# PowerConnections.net
KiCad netlist of a schematic drawn in Altium Designer
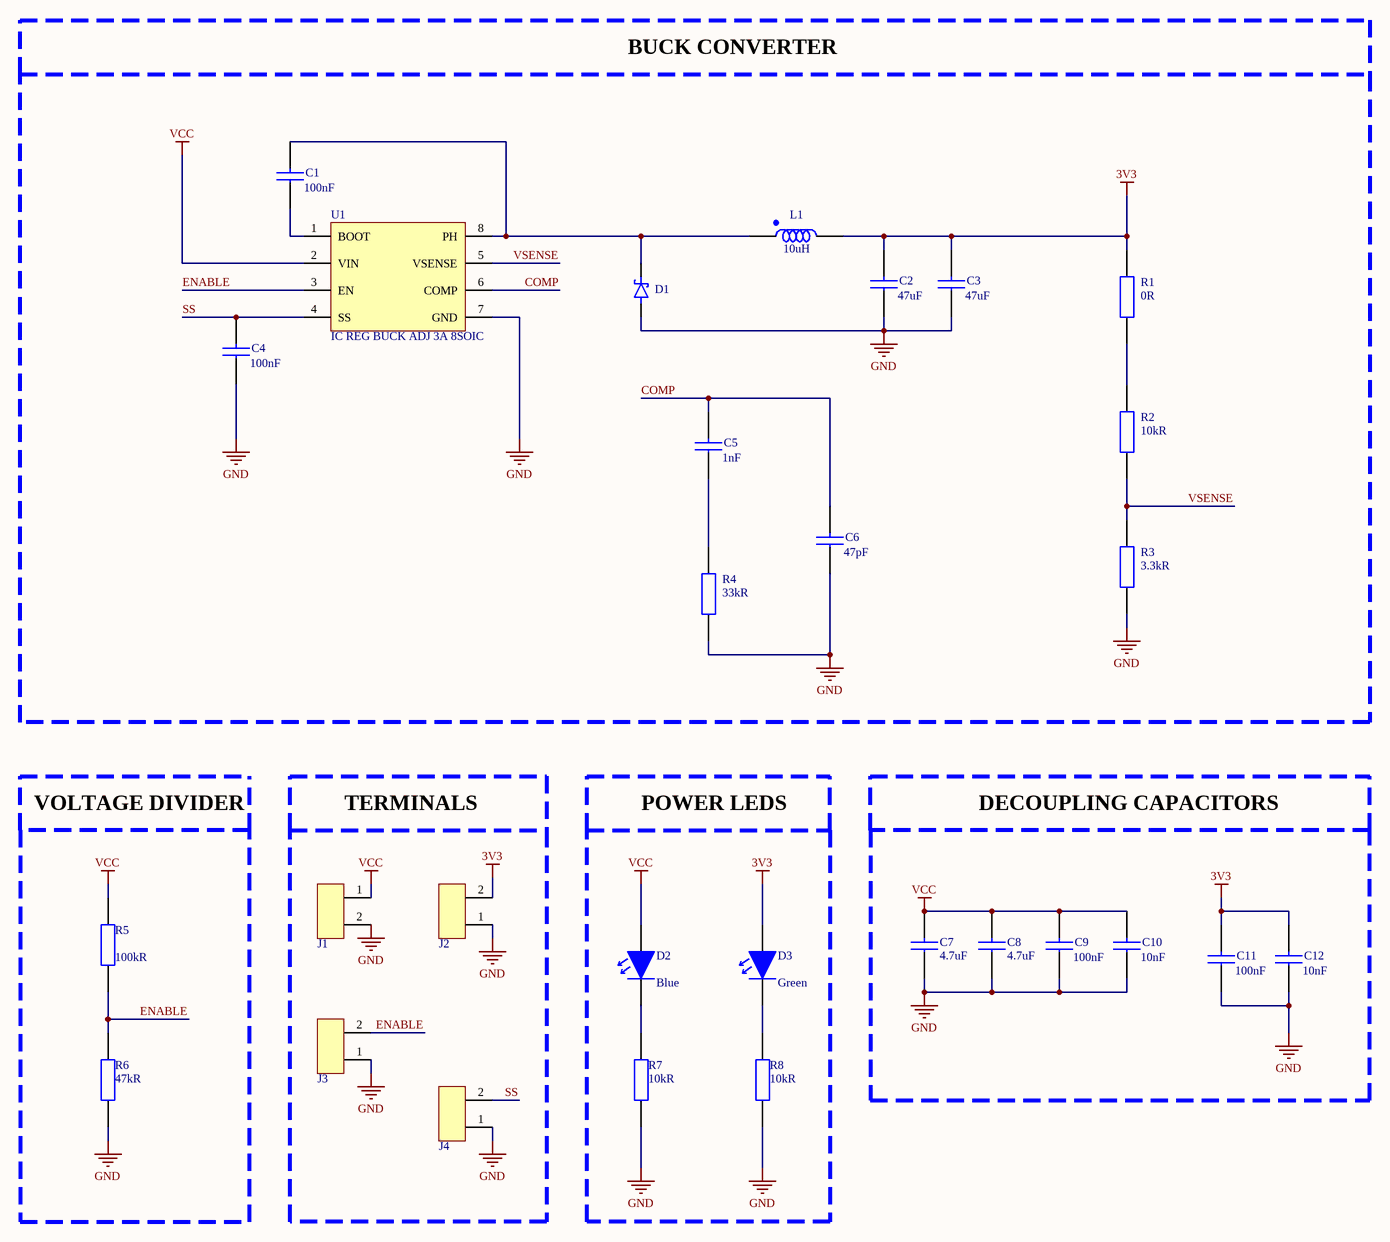
[diagram p0: PowerConnections.SchDoc]

(export (version "E")
  (design (tool "Eeschema 10.0.6"))
  (components
    (comp (ref "C1")
      (value "C1206C104J5RAC7800")
      (footprint "CAP_1206")
      (description "CAP CER 0.1UF 50V X7R 1206")
      (fields
        (field (name "MANUFACTURER") "Kyocera AVX")
        (field (name "MANUFACTURER PART NUMBER") "12065C104JAT2A")
        (field (name "CAPACITANCE") "100nF")
        (field (name "DESIGNEDBY") "Aslı Kurt")
      )
      (libsource (lib "Capacitors") (part "CAP CER 100nF 1206"))
    )
    (comp (ref "C2")
      (value "GMC31X5R476M25NT")
      (footprint "CAP_1206")
      (description "CAP CER 47UF 25V X5R 1206")
      (fields
        (field (name "MANUFACTURER") "Cal-Chip Electronics")
        (field (name "TOLERANCE") "20%")
        (field (name "CAPACITANCE") "47uF")
        (field (name "DESIGNEDBY") "Aslı Kurt")
      )
      (libsource (lib "Capacitors") (part "CAP CER 47uF 1206"))
    )
    (comp (ref "C3")
      (value "GMC31X5R476M25NT")
      (footprint "CAP_1206")
      (description "CAP CER 47UF 25V X5R 1206")
      (fields
        (field (name "MANUFACTURER") "Cal-Chip Electronics")
        (field (name "TOLERANCE") "20%")
        (field (name "CAPACITANCE") "47uF")
        (field (name "DESIGNEDBY") "Aslı Kurt")
      )
      (libsource (lib "Capacitors") (part "CAP CER 47uF 1206"))
    )
    (comp (ref "C4")
      (value "C1206C104J5RAC7800")
      (footprint "CAP_1206")
      (description "CAP CER 0.1UF 50V X7R 1206")
      (fields
        (field (name "MANUFACTURER") "Kyocera AVX")
        (field (name "MANUFACTURER PART NUMBER") "12065C104JAT2A")
        (field (name "CAPACITANCE") "100nF")
        (field (name "DESIGNEDBY") "Aslı Kurt")
      )
      (libsource (lib "Capacitors") (part "CAP CER 100nF 1206"))
    )
    (comp (ref "C5")
      (value "C3216C0G2J102J085AA")
      (footprint "CAP_1206")
      (description "CAP CER 1nF 1206")
      (fields
        (field (name "MANUFACTURER") "TDK")
        (field (name "CAPACITANCE") "1nF")
        (field (name "DESIGNEDBY") "Aslı Kurt")
      )
      (libsource (lib "Capacitors") (part "CAP CER 1nF 1206"))
    )
    (comp (ref "C6")
      (value "C1206C470J5GAC7800")
      (footprint "CAP_1206")
      (description "CAP CER 47PF 50V C0G/NP0 1206")
      (fields
        (field (name "MANUFACTURER") "KEMET")
        (field (name "MANUFACTURER PART NUMBER") "C1206C470J5GACTU")
        (field (name "CAPACITANCE") "47pF")
      )
      (libsource (lib "Capacitors") (part "CAP CER 47pF 1206"))
    )
    (comp (ref "C7")
      (value "CL21A475KAQNNNE")
      (footprint "CAP_0805")
      (description "CAP CER 4.7uF %10 0805")
      (fields
        (field (name "MANUFACTURER") "Samsung")
        (field (name "TOLERANCE") "10%")
        (field (name "CAPACITANCE") "4.7uF")
        (field (name "DESIGNED BY") "BERK")
      )
      (libsource (lib "Capacitors") (part "CAP CER 4.7uF 0805"))
    )
    (comp (ref "C8")
      (value "CL21A475KAQNNNE")
      (footprint "CAP_0805")
      (description "CAP CER 4.7uF %10 0805")
      (fields
        (field (name "MANUFACTURER") "Samsung")
        (field (name "TOLERANCE") "10%")
        (field (name "CAPACITANCE") "4.7uF")
        (field (name "DESIGNED BY") "BERK")
      )
      (libsource (lib "Capacitors") (part "CAP CER 4.7uF 0805"))
    )
    (comp (ref "C9")
      (value "C1206C104J5RAC7800")
      (footprint "CAP_1206")
      (description "CAP CER 0.1UF 50V X7R 1206")
      (fields
        (field (name "MANUFACTURER") "Kyocera AVX")
        (field (name "MANUFACTURER PART NUMBER") "12065C104JAT2A")
        (field (name "CAPACITANCE") "100nF")
        (field (name "DESIGNEDBY") "Aslı Kurt")
      )
      (libsource (lib "Capacitors") (part "CAP CER 100nF 1206"))
    )
    (comp (ref "C10")
      (value "C3216C0G2J103J160AA")
      (footprint "CAP_1206")
      (description "CAP CER 10nF 1206")
      (fields
        (field (name "MANUFACTURER") "TDK")
        (field (name "CAPACITANCE") "10nF")
        (field (name "DESIGNEDBY") "Aslı Kurt")
      )
      (libsource (lib "Capacitors") (part "CAP CER 10nF 1206"))
    )
    (comp (ref "C11")
      (value "C1206C104J5RAC7800")
      (footprint "CAP_1206")
      (description "CAP CER 0.1UF 50V X7R 1206")
      (fields
        (field (name "MANUFACTURER") "Kyocera AVX")
        (field (name "MANUFACTURER PART NUMBER") "12065C104JAT2A")
        (field (name "CAPACITANCE") "100nF")
        (field (name "DESIGNEDBY") "Aslı Kurt")
      )
      (libsource (lib "Capacitors") (part "CAP CER 100nF 1206"))
    )
    (comp (ref "C12")
      (value "C3216C0G2J103J160AA")
      (footprint "CAP_1206")
      (description "CAP CER 10nF 1206")
      (fields
        (field (name "MANUFACTURER") "TDK")
        (field (name "CAPACITANCE") "10nF")
        (field (name "DESIGNEDBY") "Aslı Kurt")
      )
      (libsource (lib "Capacitors") (part "CAP CER 10nF 1206"))
    )
    (comp (ref "D1")
      (value "B340AE-13")
      (footprint "SMA")
      (description "Rectifier Diode Schottky 40V 3A 2-Pin SMA T/R")
      (fields (field (name "MANUFACTURER") "Diodes") (field (name "DESIGNEDBY") "Aslı Kurt"))
      (libsource (lib "Diodes") (part "B340A"))
    )
    (comp (ref "D2")
      (value "150120BS75000")
      (footprint "LED_BLUE_1206")
      (description "Led, Blue, 470 Nm, 3.2 V, 30 Ma, 145 Mcd Rohs Compliant: Yes ¦Wurth Elektronik 150120BS75000")
      (fields
        (field (name "MANUFACTURER") "Wurth Electronics")
        (field (name "COLOR") "Blue")
        (field (name "DESIGNEDBY") "Aslı Kurt")
      )
      (libsource (lib "Diodes") (part "LED BLUE 1206"))
    )
    (comp (ref "D3")
      (value "150120GS75000")
      (footprint "LED_GREEN_1206")
      (description "WL-SMCW SMT Mono-Color Chip LED Waterclear")
      (fields
        (field (name "MANUFACTURER") "Wurth Electronics")
        (field (name "COLOR") "Green")
        (field (name "DESIGNEDBY") "Aslı Kurt")
      )
      (libsource (lib "Diodes") (part "LED GREEN 1206"))
    )
    (comp (ref "J1")
      (value "282836-2")
      (footprint "TERMINAL")
      (description "Connector, Terminal Block; Wire Receptacle; 2 Pos.; 16-30 AWG; 0.197 in. CL; Sid")
      (fields
        (field (name "MANUFACTURER") "TE Connectivity")
        (field (name "VOLTAGE") "300V")
        (field (name "DESIGNED BY") "Aslı Kurt")
      )
      (libsource (lib "") (part "2x1 TERMINAL 5mm_1"))
    )
    (comp (ref "J2")
      (value "282836-2")
      (footprint "TERMINAL")
      (description "Connector, Terminal Block; Wire Receptacle; 2 Pos.; 16-30 AWG; 0.197 in. CL; Sid")
      (fields
        (field (name "MANUFACTURER") "TE Connectivity")
        (field (name "VOLTAGE") "300V")
        (field (name "DESIGNED BY") "Aslı Kurt")
      )
      (libsource (lib "Connectors") (part "2x1 TERMINAL 5mm"))
    )
    (comp (ref "J3")
      (value "2x1 Male Header 2.54mm")
      (footprint "2x1 Male Header 2.54mm")
      (libsource (lib "Connectors") (part "2x1 Male Header 2.54mm"))
    )
    (comp (ref "J4")
      (value "2x1 Male Header 2.54mm")
      (footprint "2x1 Male Header 2.54mm")
      (libsource (lib "Connectors") (part "2x1 Male Header 2.54mm"))
    )
    (comp (ref "L1")
      (value "SRI1004")
      (footprint "IND_1010")
      (description "10uH 10X10 4.8A - SMD Güç Bobini - SRI1004")
      (fields
        (field (name "TOLERANCE") "20%")
        (field (name "INDUCTANCE") "10uH")
        (field (name "DESIGNEDBY") "Aslı Kurt")
      )
      (libsource (lib "Inductors") (part "IND 10uH"))
    )
    (comp (ref "R1")
      (value "PMR18EZPJ000")
      (footprint "RES_1206")
      (description "Res Thick Film 1206 0 Ohm 5% Molded SMD Paper T/R")
      (fields
        (field (name "MANUFACTURER") "Rohm")
        (field (name "RESISTANCE") "0R")
        (field (name "DESIGNEDBY") "Aslı Kurt")
      )
      (libsource (lib "Resistors") (part "RES 0 OHM 1206"))
    )
    (comp (ref "R2")
      (value "RC1206JR-0710KL")
      (footprint "RES_1206")
      (description "RES 10K OHM 5% 1/4W 1206")
      (fields
        (field (name "MANUFACTURER") "Yageo")
        (field (name "TOLERANCE") "5%")
        (field (name "RESISTANCE") "10kR")
        (field (name "DESIGNEDBY") "Aslı Kurt")
      )
      (libsource (lib "Resistors") (part "RES 10K OHM 1206"))
    )
    (comp (ref "R3")
      (value "RC1206JR-073K3L")
      (footprint "RES_1206")
      (description "RES 3.3K OHM 5% 1/4W 1206")
      (fields
        (field (name "MANUFACTURER") "Yageo")
        (field (name "RESISTANCE") "3.3kR")
        (field (name "DESIGNEDBY") "Aslı Kurt")
      )
      (libsource (lib "Resistors") (part "RES 3K3 OHM 1206"))
    )
    (comp (ref "R4")
      (value "RES 33K OHM 5% 1/4W 1206")
      (footprint "RES_1206")
      (description "SMD Chip Resistor, 33 kOhm, ï¿½ 5%, 250 mW, 1206 [3216 Metric], Thick Film, General Purpose")
      (fields
        (field (name "MANUFACTURER") "Yageo")
        (field (name "MANUFACTURER PART NUMBER") "RC1206JR-0733KL")
        (field (name "RESISTANCE") "33kR")
        (field (name "DESIGNEDBY") "Aslı Kurt")
      )
      (libsource (lib "Resistors") (part "RES 33K OHM 1206"))
    )
    (comp (ref "R5")
      (value "RC1206JR-07100KL")
      (footprint "RES_1206")
      (description "SMD Chip Resistor, 100 kOhm, ï¿½ 5%, 250 mW, 1206 [3216 Metric], Thick Film, General Purpose")
      (fields
        (field (name "MANUFACTURER") "Yageo")
        (field (name "RESISTANCE") "100kR")
        (field (name "DESIGNEDBY") "Aslı Kurt")
      )
      (libsource (lib "MyLibrary") (part "RES 100K OHM 1206 1/4W"))
    )
    (comp (ref "R6")
      (value "RES 47K OHM 5% 1/4W 1206")
      (footprint "RES_1206")
      (description "SMD Chip Resistor, 47 kOhm, ï¿½ 5%, 250 mW, 1206 [3216 Metric], Thick Film, General Purpose")
      (fields
        (field (name "MANUFACTURER") "Yageo")
        (field (name "MANUFACTURER PART NUMBER") "RC1206JR-0747KL")
        (field (name "RESISTANCE") "47kR")
        (field (name "DESIGNEDBY") "Aslı Kurt")
      )
      (libsource (lib "MyLibrary") (part "RES 47K OHM 1206 1/4W"))
    )
    (comp (ref "R7")
      (value "RC1206JR-0710KL")
      (footprint "RES_1206")
      (description "RES 10K OHM 5% 1/4W 1206")
      (fields
        (field (name "MANUFACTURER") "Yageo")
        (field (name "TOLERANCE") "5%")
        (field (name "RESISTANCE") "10kR")
        (field (name "DESIGNEDBY") "Aslı Kurt")
      )
      (libsource (lib "MyLibrary") (part "RES 10K OHM 1206 1/4W"))
    )
    (comp (ref "R8")
      (value "RC1206JR-0710KL")
      (footprint "RES_1206")
      (description "RES 10K OHM 5% 1/4W 1206")
      (fields
        (field (name "MANUFACTURER") "Yageo")
        (field (name "TOLERANCE") "5%")
        (field (name "RESISTANCE") "10kR")
        (field (name "DESIGNEDBY") "Aslı Kurt")
      )
      (libsource (lib "MyLibrary") (part "RES 10K OHM 1206 1/4W"))
    )
    (comp (ref "U1")
      (value "IC REG BUCK ADJ 3A 8SOIC")
      (footprint "SOIC8_PAD")
      (description "3.5V to 28V Input, 3A, 570kHz Step-Down Converter with Eco-mode 8-SOIC -40 to 150")
      (fields
        (field (name "MANUFACTURER") "Texas Instruments")
        (field (name "MANUFACTURER PART NUMBER") "TPS54331DR")
        (field (name "DESIGNEDBY") "Aslı Kurt")
      )
      (libsource (lib "Regulators") (part "TPS54331DR"))
    )
  )
  (nets
    (net (code "1") (name "/COMP") (class "Default")
      (node (ref "C5") (pin "2") (pinfunction "2_2") (pintype "passive"))
      (node (ref "C6") (pin "2") (pinfunction "2_2") (pintype "passive"))
      (node (ref "U1") (pin "6") (pinfunction "COMP_6") (pintype "passive"))
    )
    (net (code "2") (name "/ENABLE") (class "Default")
      (node (ref "J3") (pin "2") (pinfunction "2_2") (pintype "power_in"))
      (node (ref "R5") (pin "1") (pinfunction "1_1") (pintype "passive"))
      (node (ref "R6") (pin "2") (pinfunction "2_2") (pintype "passive"))
      (node (ref "U1") (pin "3") (pinfunction "EN_3") (pintype "passive"))
    )
    (net (code "3") (name "/SS") (class "Default")
      (node (ref "C4") (pin "2") (pinfunction "2_2") (pintype "passive"))
      (node (ref "J4") (pin "2") (pinfunction "2_2") (pintype "power_in"))
      (node (ref "U1") (pin "4") (pinfunction "SS_4") (pintype "passive"))
    )
    (net (code "4") (name "/VSENSE") (class "Default")
      (node (ref "R2") (pin "1") (pinfunction "1_1") (pintype "passive"))
      (node (ref "R3") (pin "2") (pinfunction "2_2") (pintype "passive"))
      (node (ref "U1") (pin "5") (pinfunction "VSENSE_5") (pintype "passive"))
    )
    (net (code "5") (name "3V3") (class "Default")
      (node (ref "C11") (pin "2") (pinfunction "2_2") (pintype "passive"))
      (node (ref "C12") (pin "2") (pinfunction "2_2") (pintype "passive"))
      (node (ref "C2") (pin "2") (pinfunction "2_2") (pintype "passive"))
      (node (ref "C3") (pin "2") (pinfunction "2_2") (pintype "passive"))
      (node (ref "D3") (pin "2") (pinfunction "2_2") (pintype "power_in"))
      (node (ref "J2") (pin "2") (pinfunction "2_2") (pintype "passive"))
      (node (ref "L1") (pin "2") (pinfunction "2_2") (pintype "passive"))
      (node (ref "R1") (pin "2") (pinfunction "2_2") (pintype "passive"))
    )
    (net (code "6") (name "GND") (class "Default")
      (node (ref "C10") (pin "1") (pinfunction "1_1") (pintype "passive"))
      (node (ref "C11") (pin "1") (pinfunction "1_1") (pintype "passive"))
      (node (ref "C12") (pin "1") (pinfunction "1_1") (pintype "passive"))
      (node (ref "C2") (pin "1") (pinfunction "1_1") (pintype "passive"))
      (node (ref "C3") (pin "1") (pinfunction "1_1") (pintype "passive"))
      (node (ref "C4") (pin "1") (pinfunction "1_1") (pintype "passive"))
      (node (ref "C6") (pin "1") (pinfunction "1_1") (pintype "passive"))
      (node (ref "C7") (pin "1") (pinfunction "1_1") (pintype "passive"))
      (node (ref "C8") (pin "1") (pinfunction "1_1") (pintype "passive"))
      (node (ref "C9") (pin "1") (pinfunction "1_1") (pintype "passive"))
      (node (ref "D1") (pin "1") (pinfunction "1_1") (pintype "passive"))
      (node (ref "J1") (pin "2") (pinfunction "2_2") (pintype "passive"))
      (node (ref "J2") (pin "1") (pinfunction "1_1") (pintype "passive"))
      (node (ref "J3") (pin "1") (pinfunction "1_1") (pintype "power_in"))
      (node (ref "J4") (pin "1") (pinfunction "1_1") (pintype "power_in"))
      (node (ref "R3") (pin "1") (pinfunction "1_1") (pintype "passive"))
      (node (ref "R4") (pin "1") (pinfunction "1_1") (pintype "passive"))
      (node (ref "R6") (pin "1") (pinfunction "1_1") (pintype "passive"))
      (node (ref "R7") (pin "1") (pinfunction "1_1") (pintype "passive"))
      (node (ref "R8") (pin "1") (pinfunction "1_1") (pintype "passive"))
      (node (ref "U1") (pin "7") (pinfunction "GND_7") (pintype "passive"))
    )
    (net (code "7") (name "Net-(C5-Pad1)") (class "Default")
      (node (ref "C5") (pin "1") (pinfunction "1_1") (pintype "passive"))
      (node (ref "R4") (pin "2") (pinfunction "2_2") (pintype "passive"))
    )
    (net (code "8") (name "Net-(D2-Pad1)") (class "Default")
      (node (ref "D2") (pin "1") (pinfunction "1_1") (pintype "power_in"))
      (node (ref "R7") (pin "2") (pinfunction "2_2") (pintype "passive"))
    )
    (net (code "9") (name "Net-(D3-Pad1)") (class "Default")
      (node (ref "D3") (pin "1") (pinfunction "1_1") (pintype "power_in"))
      (node (ref "R8") (pin "2") (pinfunction "2_2") (pintype "passive"))
    )
    (net (code "10") (name "Net-(R1-Pad1)") (class "Default")
      (node (ref "R1") (pin "1") (pinfunction "1_1") (pintype "passive"))
      (node (ref "R2") (pin "2") (pinfunction "2_2") (pintype "passive"))
    )
    (net (code "11") (name "Net-(U1-BOOT)") (class "Default")
      (node (ref "C1") (pin "1") (pinfunction "1_1") (pintype "passive"))
      (node (ref "U1") (pin "1") (pinfunction "BOOT_1") (pintype "passive"))
    )
    (net (code "12") (name "Net-(U1-PH)") (class "Default")
      (node (ref "C1") (pin "2") (pinfunction "2_2") (pintype "passive"))
      (node (ref "D1") (pin "2") (pinfunction "2_2") (pintype "passive"))
      (node (ref "L1") (pin "1") (pinfunction "1_1") (pintype "passive"))
      (node (ref "U1") (pin "8") (pinfunction "PH_8") (pintype "passive"))
    )
    (net (code "13") (name "VCC") (class "Default")
      (node (ref "C10") (pin "2") (pinfunction "2_2") (pintype "passive"))
      (node (ref "C7") (pin "2") (pinfunction "2_2") (pintype "passive"))
      (node (ref "C8") (pin "2") (pinfunction "2_2") (pintype "passive"))
      (node (ref "C9") (pin "2") (pinfunction "2_2") (pintype "passive"))
      (node (ref "D2") (pin "2") (pinfunction "2_2") (pintype "power_in"))
      (node (ref "J1") (pin "1") (pinfunction "1_1") (pintype "passive"))
      (node (ref "R5") (pin "2") (pinfunction "2_2") (pintype "passive"))
      (node (ref "U1") (pin "2") (pinfunction "VIN_2") (pintype "passive"))
    )
  )
)
